# Supplies.net
KiCad netlist of a schematic drawn in Altium Designer
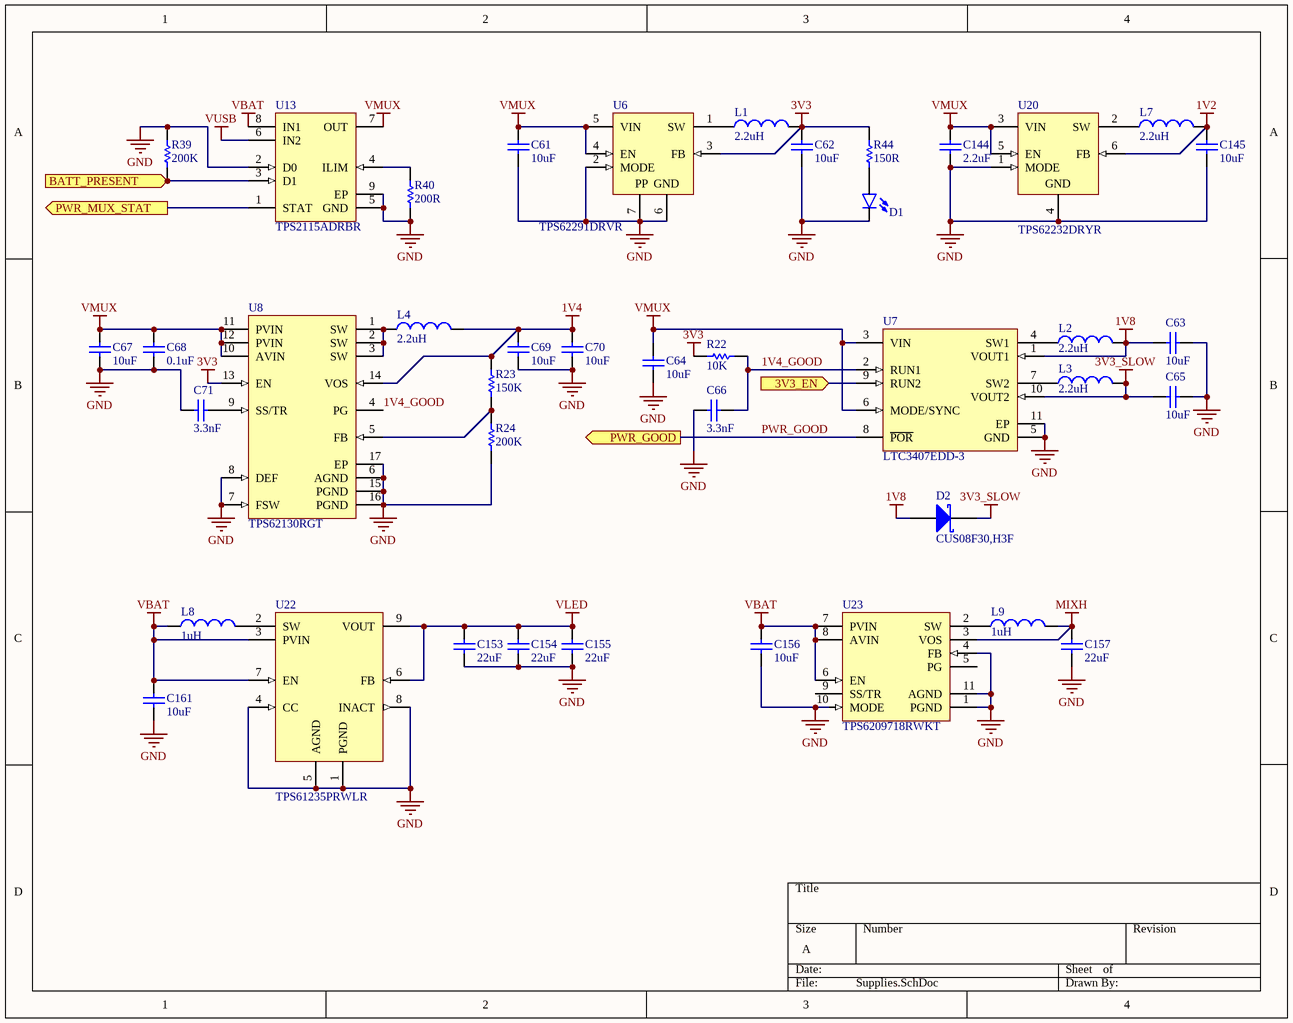
[diagram p0: Supplies.SchDoc]

(export (version "E")
  (design (tool "Eeschema 10.0.6"))
  (components
    (comp (ref "C61")
      (value "10uF")
      (footprint "C0402[1005X55]")
      (description "10uF 6.3V 20% 0402 (1005 Metric)")
      (fields (field (name "TOLERANCE") "20%") (field (name "PARTNUMBER") "GRM155R60J106ME44D"))
      (libsource (lib "Capacitors") (part "CAP_10uF_6.3V_0402_20%"))
    )
    (comp (ref "C62")
      (value "10uF")
      (footprint "C0402[1005X55]")
      (description "10uF 6.3V 20% 0402 (1005 Metric)")
      (fields (field (name "TOLERANCE") "20%") (field (name "PARTNUMBER") "GRM155R60J106ME44D"))
      (libsource (lib "Capacitors") (part "CAP_10uF_6.3V_0402_20%"))
    )
    (comp (ref "C63")
      (value "10uF")
      (footprint "C0402[1005X55]")
      (description "10uF 6.3V 20% 0402 (1005 Metric)")
      (fields (field (name "PARTNUMBER") "GRM155R60J106ME44D") (field (name "MANUFACTURER") "Murata"))
      (libsource (lib "Capacitors") (part "CAP_10uF_6.3V_0402_20%"))
    )
    (comp (ref "C64")
      (value "10uF")
      (footprint "C0402[1005X55]")
      (description "10uF 6.3V 20% 0402 (1005 Metric)")
      (fields (field (name "PARTNUMBER") "GRM155R60J106ME44D") (field (name "MANUFACTURER") "Murata"))
      (libsource (lib "Capacitors") (part "CAP_10uF_6.3V_0402_20%"))
    )
    (comp (ref "C65")
      (value "10uF")
      (footprint "C0402[1005X55]")
      (description "10uF 6.3V 20% 0402 (1005 Metric)")
      (fields (field (name "PARTNUMBER") "GRM155R60J106ME44D") (field (name "MANUFACTURER") "Murata"))
      (libsource (lib "Capacitors") (part "CAP_10uF_6.3V_0402_20%"))
    )
    (comp (ref "C66")
      (value "3.3nF")
      (footprint "C0402[1005X55]")
      (description "3.3nF 50V 10% 0402 (1005 Metric)")
      (fields (field (name "PARTNUMBER") "GRM155R71H332KA01D") (field (name "MANUFACTURER") "Murata"))
      (libsource (lib "Capacitors") (part "CAP_3.3nF_50V_0402_10%"))
    )
    (comp (ref "C67")
      (value "10uF")
      (footprint "C0402[1005X55]")
      (description "10uF 6.3V 20% 0402 (1005 Metric)")
      (fields (field (name "PARTNUMBER") "GRM155R60J106ME44D") (field (name "MANUFACTURER") "Murata"))
      (libsource (lib "Capacitors") (part "CAP_10uF_6.3V_0402_20%"))
    )
    (comp (ref "C68")
      (value "0.1uF")
      (footprint "C0402[1005X55]")
      (description "0.1uF 6.3V 10% 0402 (1005 Metric)")
      (fields (field (name "PARTNUMBER") "GRM155R70J104KA01D") (field (name "MANUFACTURER") "Murata"))
      (libsource (lib "Capacitors") (part "CAP_0.1uF_6.3V_0402_10%"))
    )
    (comp (ref "C69")
      (value "10uF")
      (footprint "C0402[1005X55]")
      (description "10uF 6.3V 20% 0402 (1005 Metric)")
      (fields (field (name "PARTNUMBER") "GRM155R60J106ME44D") (field (name "MANUFACTURER") "Murata"))
      (libsource (lib "Capacitors") (part "CAP_10uF_6.3V_0402_20%"))
    )
    (comp (ref "C70")
      (value "10uF")
      (footprint "C0402[1005X55]")
      (description "10uF 6.3V 20% 0402 (1005 Metric)")
      (fields (field (name "PARTNUMBER") "GRM155R60J106ME44D") (field (name "MANUFACTURER") "Murata"))
      (libsource (lib "Capacitors") (part "CAP_10uF_6.3V_0402_20%"))
    )
    (comp (ref "C71")
      (value "3.3nF")
      (footprint "C0402[1005X55]")
      (description "3.3nF 50V 10% 0402 (1005 Metric)")
      (fields (field (name "PARTNUMBER") "GRM155R71H332KA01D") (field (name "MANUFACTURER") "Murata"))
      (libsource (lib "Capacitors") (part "CAP_3.3nF_50V_0402_10%"))
    )
    (comp (ref "C144")
      (value "2.2uF")
      (footprint "C0402[1005X55]")
      (description "2.2uF 6.3V 20% 0402 (1005 Metric)")
      (fields (field (name "PARTNUMBER") "GRM155R60J225ME15D") (field (name "MANUFACTURER") "Murata"))
      (libsource (lib "Capacitors") (part "CAP_2.2uF_6.3V_0402_20%"))
    )
    (comp (ref "C145")
      (value "10uF")
      (footprint "C0402[1005X55]")
      (description "10uF 6.3V 20% 0402 (1005 Metric)")
      (fields (field (name "PARTNUMBER") "GRM155R60J106ME44D") (field (name "MANUFACTURER") "Murata"))
      (libsource (lib "Capacitors") (part "CAP_10uF_6.3V_0402_20%"))
    )
    (comp (ref "C153")
      (value "22uF")
      (footprint "C0603[1608X92]")
      (description "22uF 6.3V 10% 0603 (1608 Metric)")
      (fields (field (name "PARTNUMBER") "GRT188R60J226ME13D") (field (name "MANUFACTURER") "Murata"))
      (libsource (lib "Capacitors") (part "CAP_22uF_6.3V_0603_10%"))
    )
    (comp (ref "C154")
      (value "22uF")
      (footprint "C0603[1608X92]")
      (description "22uF 6.3V 10% 0603 (1608 Metric)")
      (fields (field (name "PARTNUMBER") "GRT188R60J226ME13D") (field (name "MANUFACTURER") "Murata"))
      (libsource (lib "Capacitors") (part "CAP_22uF_6.3V_0603_10%"))
    )
    (comp (ref "C155")
      (value "22uF")
      (footprint "C0603[1608X92]")
      (description "22uF 6.3V 10% 0603 (1608 Metric)")
      (fields (field (name "PARTNUMBER") "GRT188R60J226ME13D") (field (name "MANUFACTURER") "Murata"))
      (libsource (lib "Capacitors") (part "CAP_22uF_6.3V_0603_10%"))
    )
    (comp (ref "C156")
      (value "10uF")
      (footprint "C0402[1005X55]")
      (description "10uF 6.3V 20% 0402 (1005 Metric)")
      (fields (field (name "PARTNUMBER") "GRM155R60J106ME44D") (field (name "MANUFACTURER") "Murata"))
      (libsource (lib "Capacitors") (part "CAP_10uF_6.3V_0402_20%"))
    )
    (comp (ref "C157")
      (value "22uF")
      (footprint "C0603[1608X92]")
      (description "22uF 6.3V 10% 0603 (1608 Metric)")
      (fields (field (name "PARTNUMBER") "GRT188R60J226ME13D") (field (name "MANUFACTURER") "Murata"))
      (libsource (lib "Capacitors") (part "CAP_22uF_6.3V_0603_10%"))
    )
    (comp (ref "C161")
      (value "10uF")
      (footprint "C0402[1005X55]")
      (description "10uF 6.3V 20% 0402 (1005 Metric)")
      (fields (field (name "PARTNUMBER") "GRM155R60J106ME44D") (field (name "MANUFACTURER") "Murata"))
      (libsource (lib "Capacitors") (part "CAP_10uF_6.3V_0402_20%"))
    )
    (comp (ref "D1")
      (value "LED_0603_BLUE_5mA")
      (footprint "LED0603")
      (fields (field (name "PARTNUMBER") "LTST-C193TBKT-5A") (field (name "MANUFACTURER") "Lite-On Inc."))
      (libsource (lib "LEDs") (part "LED_0603_BLUE_5mA"))
    )
    (comp (ref "D2")
      (value "CUS08F30,H3F")
      (footprint "SOD-323")
      (fields (field (name "MANUFACTURER") "Toshiba"))
      (libsource (lib "Diodes") (part "CUS08F30,H3F"))
    )
    (comp (ref "L1")
      (value "2.2uH")
      (footprint "IND0805")
      (description "2.2uH 20% 1.7A 0805")
      (fields (field (name "PARTNUMBER") "LQM21PN2R2MGHL") (field (name "MANUFACTURER") "Murata"))
      (libsource (lib "Inductors") (part "IND_2.2uH_1.7A_0805_20%"))
    )
    (comp (ref "L2")
      (value "2.2uH")
      (footprint "IND0603")
      (description "2.2uH 20% 750mA 0603")
      (fields (field (name "PARTNUMBER") "LQM18PZ2R2MCHD") (field (name "MANUFACTURER") "Murata"))
      (libsource (lib "Inductors") (part "IND_2.2uH_750mA_0603_20%"))
    )
    (comp (ref "L3")
      (value "2.2uH")
      (footprint "IND0603")
      (description "2.2uH 20% 750mA 0603")
      (fields (field (name "PARTNUMBER") "LQM18PZ2R2MCHD") (field (name "MANUFACTURER") "Murata"))
      (libsource (lib "Inductors") (part "IND_2.2uH_750mA_0603_20%"))
    )
    (comp (ref "L4")
      (value "2.2uH")
      (footprint "IND1008")
      (description "2.2uH 20% 3.3A 1008")
      (fields (field (name "PARTNUMBER") "DFE252012F-2R2M=P2") (field (name "MANUFACTURER") "Murata"))
      (libsource (lib "Inductors") (part "IND_2.2uH_3.3A_1008_20%"))
    )
    (comp (ref "L7")
      (value "2.2uH")
      (footprint "IND0603")
      (description "2.2uH 20% 750mA 0603")
      (fields (field (name "PARTNUMBER") "LQM18PZ2R2MCHD") (field (name "MANUFACTURER") "Murata"))
      (libsource (lib "Inductors") (part "IND_2.2uH_750mA_0603_20%"))
    )
    (comp (ref "L8")
      (value "1uH")
      (footprint "IND1008")
      (description "1uH 20% 4.7A 1008")
      (fields (field (name "PARTNUMBER") "DFE252012F-2R2M=P2") (field (name "MANUFACTURER") "Murata"))
      (libsource (lib "Inductors") (part "IND_1uH_4.7A_1008_20%"))
    )
    (comp (ref "L9")
      (value "1uH")
      (footprint "IND0805")
      (description "1uH 20% 2.3A 0805")
      (fields (field (name "PARTNUMBER") "DFE201210S-1R0M=P2") (field (name "MANUFACTURER") "Murata"))
      (libsource (lib "Inductors") (part "IND_1uH_2.3A_0805_20%"))
    )
    (comp (ref "R22")
      (value "10K")
      (footprint "R0402[1005]")
      (description "10K 0.063W 1% 0402 (1005 Metric)")
      (fields (field (name "MANUFACTURER") "KOA Speer") (field (name "PARTNUMBER") "RK73H1ETTP1002F"))
      (libsource (lib "Resistors") (part "RES_10K_0402_1%"))
    )
    (comp (ref "R23")
      (value "150K")
      (footprint "R0402[1005]")
      (description "150K 0.063W 1% 0402 (1005 Metric)")
      (fields (field (name "MANUFACTURER") "KOA Speer") (field (name "PARTNUMBER") "RK73H1ETTP1503F"))
      (libsource (lib "Resistors") (part "RES_150K_0402_1%"))
    )
    (comp (ref "R24")
      (value "200K")
      (footprint "R0402[1005]")
      (description "200K 0.063W 1% 0402 (1005 Metric)")
      (fields (field (name "MANUFACTURER") "KOA Speer") (field (name "PARTNUMBER") "RK73H1ETTP2003F"))
      (libsource (lib "Resistors") (part "RES_200K_0402_1%"))
    )
    (comp (ref "R39")
      (value "200K")
      (footprint "R0402[1005]")
      (description "200K 0.063W 1% 0402 (1005 Metric)")
      (fields (field (name "MANUFACTURER") "KOA Speer") (field (name "PARTNUMBER") "RK73H1ETTP2003F"))
      (libsource (lib "Resistors") (part "RES_200K_0402_1%"))
    )
    (comp (ref "R40")
      (value "200R")
      (footprint "R0402[1005]")
      (description "200R 0.063W 1% 0402 (1005 Metric)")
      (fields (field (name "MANUFACTURER") "KOA Speer") (field (name "PARTNUMBER") "RK73H1ETTP2000F"))
      (libsource (lib "Resistors") (part "RES_200R_0402_1%"))
    )
    (comp (ref "R44")
      (value "150R")
      (footprint "R0402[1005]")
      (description "150R 0.063W 1% 0402 (1005 Metric)")
      (fields (field (name "MANUFACTURER") "KOA Speer") (field (name "PARTNUMBER") "RK73H1ETTP1500F"))
      (libsource (lib "Resistors") (part "RES_150R_0402_1%"))
    )
    (comp (ref "U6")
      (value "TPS62291DRVR")
      (footprint "WSON-6")
      (description "Voltage Regulators - Switching Regulators 2.25MHz 1A Step-Down Cnvrtr 3.3V Output")
      (fields (field (name "MANUFACTURER") "Texas Instruments"))
      (libsource (lib "ICs") (part "TPS62291DRVR"))
    )
    (comp (ref "U7")
      (value "LTC3407EDD-3")
      (footprint "VSON-10 (3mmx3mm)")
      (fields (field (name "MANUFACTURER") "Linear Technology"))
      (libsource (lib "ICs") (part "LTC3407EDD-3"))
    )
    (comp (ref "U8")
      (value "TPS62130RGT")
      (footprint "QFN-16")
      (fields (field (name "MANUFACTURER") "Texas Instruments"))
      (libsource (lib "ICs") (part "TPS62130RGT"))
    )
    (comp (ref "U13")
      (value "TPS2115ADRBR")
      (footprint "VSON-8 (3x3MM)")
      (description "Power Switch ICs - Power Distribution Autoswitching Pwr Mux")
      (fields (field (name "MANUFACTURER") "Texas Instruments"))
      (libsource (lib "ICs") (part "TPS2115ADRBR"))
    )
    (comp (ref "U20")
      (value "TPS62232DRYR")
      (footprint "USON-6")
      (description "Switching Voltage Regulators 3 MHz Ultra Small Step Down Converter")
      (fields (field (name "MANUFACTURER") "Texas Instruments"))
      (libsource (lib "ICs") (part "TPS62232DRYR"))
    )
    (comp (ref "U22")
      (value "TPS61235PRWLR")
      (footprint "VQFN-9")
      (fields (field (name "MANUFACTURER") "Texas Instruments"))
      (libsource (lib "ICs") (part "TPS61235PRWLR"))
    )
    (comp (ref "U23")
      (value "TPS6209718RWKT")
      (footprint "VQFN-11")
      (fields (field (name "MANUFACTURER") "Texas Instruments"))
      (libsource (lib "ICs") (part "TPS6209718RWKT"))
    )
  )
  (nets
    (net (code "1") (name "/1V4_GOOD") (class "Default")
      (node (ref "C66") (pin "2") (pinfunction "2_2") (pintype "passive"))
      (node (ref "R22") (pin "2") (pinfunction "2_2") (pintype "passive"))
      (node (ref "U7") (pin "2") (pinfunction "RUN1_2") (pintype "input"))
      (node (ref "U8") (pin "4") (pinfunction "PG_4") (pintype "tri_state"))
    )
    (net (code "2") (name "/3V3_EN") (class "Default")
      (node (ref "U7") (pin "9") (pinfunction "RUN2_9") (pintype "input"))
    )
    (net (code "3") (name "/BATT_PRESENT") (class "Default")
      (node (ref "R39") (pin "1") (pinfunction "1_1") (pintype "passive"))
      (node (ref "U13") (pin "3") (pinfunction "D1_3") (pintype "input"))
    )
    (net (code "4") (name "/PWR_GOOD") (class "Default")
      (node (ref "U7") (pin "8") (pinfunction "~{POR}_8") (pintype "open_collector"))
    )
    (net (code "5") (name "/PWR_MUX_STAT") (class "Default")
      (node (ref "U13") (pin "1") (pinfunction "STAT_1") (pintype "tri_state"))
    )
    (net (code "6") (name "1V2") (class "Default")
      (node (ref "C145") (pin "2") (pinfunction "2_2") (pintype "passive"))
      (node (ref "L7") (pin "2") (pinfunction "2_2") (pintype "passive"))
      (node (ref "U20") (pin "6") (pinfunction "FB_6") (pintype "input"))
    )
    (net (code "7") (name "1V4") (class "Default")
      (node (ref "C69") (pin "2") (pinfunction "2_2") (pintype "passive"))
      (node (ref "C70") (pin "2") (pinfunction "2_2") (pintype "passive"))
      (node (ref "L4") (pin "2") (pinfunction "2_2") (pintype "passive"))
      (node (ref "R23") (pin "2") (pinfunction "2_2") (pintype "passive"))
      (node (ref "U8") (pin "14") (pinfunction "VOS_14") (pintype "input"))
    )
    (net (code "8") (name "1V8") (class "Default")
      (node (ref "C63") (pin "2") (pinfunction "2_2") (pintype "passive"))
      (node (ref "D2") (pin "2") (pinfunction "A_2") (pintype "passive"))
      (node (ref "L2") (pin "2") (pinfunction "2_2") (pintype "passive"))
      (node (ref "U7") (pin "1") (pinfunction "VOUT1_1") (pintype "input"))
    )
    (net (code "9") (name "3V3") (class "Default")
      (node (ref "C62") (pin "2") (pinfunction "2_2") (pintype "passive"))
      (node (ref "L1") (pin "2") (pinfunction "2_2") (pintype "passive"))
      (node (ref "R22") (pin "1") (pinfunction "1_1") (pintype "passive"))
      (node (ref "R44") (pin "2") (pinfunction "2_2") (pintype "passive"))
      (node (ref "U6") (pin "3") (pinfunction "FB_3") (pintype "input"))
      (node (ref "U8") (pin "13") (pinfunction "EN_13") (pintype "input"))
    )
    (net (code "10") (name "3V3_SLOW") (class "Default")
      (node (ref "C65") (pin "1") (pinfunction "1_1") (pintype "passive"))
      (node (ref "D2") (pin "1") (pinfunction "K_1") (pintype "passive"))
      (node (ref "L3") (pin "2") (pinfunction "2_2") (pintype "passive"))
      (node (ref "U7") (pin "10") (pinfunction "VOUT2_10") (pintype "input"))
    )
    (net (code "11") (name "GND") (class "Default")
      (node (ref "C144") (pin "1") (pinfunction "1_1") (pintype "passive"))
      (node (ref "C145") (pin "1") (pinfunction "1_1") (pintype "passive"))
      (node (ref "C153") (pin "1") (pinfunction "1_1") (pintype "passive"))
      (node (ref "C154") (pin "1") (pinfunction "1_1") (pintype "passive"))
      (node (ref "C155") (pin "1") (pinfunction "1_1") (pintype "passive"))
      (node (ref "C156") (pin "1") (pinfunction "1_1") (pintype "passive"))
      (node (ref "C157") (pin "1") (pinfunction "1_1") (pintype "passive"))
      (node (ref "C161") (pin "1") (pinfunction "1_1") (pintype "passive"))
      (node (ref "C61") (pin "1") (pinfunction "1_1") (pintype "passive"))
      (node (ref "C62") (pin "1") (pinfunction "1_1") (pintype "passive"))
      (node (ref "C63") (pin "1") (pinfunction "1_1") (pintype "passive"))
      (node (ref "C64") (pin "1") (pinfunction "1_1") (pintype "passive"))
      (node (ref "C65") (pin "2") (pinfunction "2_2") (pintype "passive"))
      (node (ref "C66") (pin "1") (pinfunction "1_1") (pintype "passive"))
      (node (ref "C67") (pin "1") (pinfunction "1_1") (pintype "passive"))
      (node (ref "C68") (pin "1") (pinfunction "1_1") (pintype "passive"))
      (node (ref "C69") (pin "1") (pinfunction "1_1") (pintype "passive"))
      (node (ref "C70") (pin "1") (pinfunction "1_1") (pintype "passive"))
      (node (ref "C71") (pin "1") (pinfunction "1_1") (pintype "passive"))
      (node (ref "D1") (pin "C") (pinfunction "C_C") (pintype "passive"))
      (node (ref "R24") (pin "1") (pinfunction "1_1") (pintype "passive"))
      (node (ref "R39") (pin "2") (pinfunction "2_2") (pintype "passive"))
      (node (ref "R40") (pin "1") (pinfunction "1_1") (pintype "passive"))
      (node (ref "U13") (pin "2") (pinfunction "D0_2") (pintype "input"))
      (node (ref "U13") (pin "5") (pinfunction "GND_5") (pintype "power_in"))
      (node (ref "U13") (pin "9") (pinfunction "EP_9") (pintype "power_in"))
      (node (ref "U20") (pin "1") (pinfunction "MODE_1") (pintype "input"))
      (node (ref "U20") (pin "4") (pinfunction "GND_4") (pintype "power_in"))
      (node (ref "U22") (pin "1") (pinfunction "PGND_1") (pintype "power_in"))
      (node (ref "U22") (pin "4") (pinfunction "CC_4") (pintype "input"))
      (node (ref "U22") (pin "5") (pinfunction "AGND_5") (pintype "power_in"))
      (node (ref "U22") (pin "8") (pinfunction "INACT_8") (pintype "output"))
      (node (ref "U23") (pin "1") (pinfunction "PGND_1") (pintype "power_in"))
      (node (ref "U23") (pin "10") (pinfunction "MODE_10") (pintype "input"))
      (node (ref "U23") (pin "11") (pinfunction "AGND_11") (pintype "power_in"))
      (node (ref "U23") (pin "4") (pinfunction "FB_4") (pintype "input"))
      (node (ref "U6") (pin "2") (pinfunction "MODE_2") (pintype "input"))
      (node (ref "U6") (pin "6") (pinfunction "GND_6") (pintype "power_in"))
      (node (ref "U6") (pin "7") (pinfunction "EP_7") (pintype "passive"))
      (node (ref "U7") (pin "11") (pinfunction "EP_11") (pintype "power_in"))
      (node (ref "U7") (pin "5") (pinfunction "GND_5") (pintype "power_in"))
      (node (ref "U8") (pin "15") (pinfunction "PGND_15") (pintype "power_in"))
      (node (ref "U8") (pin "16") (pinfunction "PGND_16") (pintype "power_in"))
      (node (ref "U8") (pin "17") (pinfunction "EP_17") (pintype "power_in"))
      (node (ref "U8") (pin "6") (pinfunction "AGND_6") (pintype "power_in"))
      (node (ref "U8") (pin "7") (pinfunction "FSW_7") (pintype "input"))
      (node (ref "U8") (pin "8") (pinfunction "DEF_8") (pintype "input"))
    )
    (net (code "12") (name "MIXH") (class "Default")
      (node (ref "C157") (pin "2") (pinfunction "2_2") (pintype "passive"))
      (node (ref "L9") (pin "2") (pinfunction "2_2") (pintype "passive"))
      (node (ref "U23") (pin "3") (pinfunction "VOS_3") (pintype "passive"))
    )
    (net (code "13") (name "Net-(D1-PadA)") (class "Default")
      (node (ref "D1") (pin "A") (pinfunction "A_A") (pintype "passive"))
      (node (ref "R44") (pin "1") (pinfunction "1_1") (pintype "passive"))
    )
    (net (code "14") (name "Net-(L4-Pad1)") (class "Default")
      (node (ref "L4") (pin "1") (pinfunction "1_1") (pintype "passive"))
      (node (ref "U8") (pin "1") (pinfunction "SW_1") (pintype "power_in"))
      (node (ref "U8") (pin "2") (pinfunction "SW_2") (pintype "power_in"))
      (node (ref "U8") (pin "3") (pinfunction "SW_3") (pintype "power_in"))
    )
    (net (code "15") (name "Net-(U6-SW)") (class "Default")
      (node (ref "L1") (pin "1") (pinfunction "1_1") (pintype "passive"))
      (node (ref "U6") (pin "1") (pinfunction "SW_1") (pintype "power_in"))
    )
    (net (code "16") (name "Net-(U7-SW1)") (class "Default")
      (node (ref "L2") (pin "1") (pinfunction "1_1") (pintype "passive"))
      (node (ref "U7") (pin "4") (pinfunction "SW1_4") (pintype "power_in"))
    )
    (net (code "17") (name "Net-(U7-SW2)") (class "Default")
      (node (ref "L3") (pin "1") (pinfunction "1_1") (pintype "passive"))
      (node (ref "U7") (pin "7") (pinfunction "SW2_7") (pintype "power_in"))
    )
    (net (code "18") (name "Net-(U8-FB)") (class "Default")
      (node (ref "R23") (pin "1") (pinfunction "1_1") (pintype "passive"))
      (node (ref "R24") (pin "2") (pinfunction "2_2") (pintype "passive"))
      (node (ref "U8") (pin "5") (pinfunction "FB_5") (pintype "input"))
    )
    (net (code "19") (name "Net-(U8-SS{slash}TR)") (class "Default")
      (node (ref "C71") (pin "2") (pinfunction "2_2") (pintype "passive"))
      (node (ref "U8") (pin "9") (pinfunction "SS/TR_9") (pintype "input"))
    )
    (net (code "20") (name "Net-(U13-ILIM)") (class "Default")
      (node (ref "R40") (pin "2") (pinfunction "2_2") (pintype "passive"))
      (node (ref "U13") (pin "4") (pinfunction "ILIM_4") (pintype "input"))
    )
    (net (code "21") (name "Net-(U20-SW)") (class "Default")
      (node (ref "L7") (pin "1") (pinfunction "1_1") (pintype "passive"))
      (node (ref "U20") (pin "2") (pinfunction "SW_2") (pintype "power_in"))
    )
    (net (code "22") (name "Net-(U22-SW)") (class "Default")
      (node (ref "L8") (pin "2") (pinfunction "2_2") (pintype "passive"))
      (node (ref "U22") (pin "2") (pinfunction "SW_2") (pintype "power_in"))
    )
    (net (code "23") (name "Net-(U23-SW)") (class "Default")
      (node (ref "L9") (pin "1") (pinfunction "1_1") (pintype "passive"))
      (node (ref "U23") (pin "2") (pinfunction "SW_2") (pintype "power_in"))
    )
    (net (code "24") (name "VBAT") (class "Default")
      (node (ref "C156") (pin "2") (pinfunction "2_2") (pintype "passive"))
      (node (ref "C161") (pin "2") (pinfunction "2_2") (pintype "passive"))
      (node (ref "L8") (pin "1") (pinfunction "1_1") (pintype "passive"))
      (node (ref "U13") (pin "8") (pinfunction "IN1_8") (pintype "power_in"))
      (node (ref "U22") (pin "3") (pinfunction "PVIN_3") (pintype "power_in"))
      (node (ref "U22") (pin "7") (pinfunction "EN_7") (pintype "input"))
      (node (ref "U23") (pin "6") (pinfunction "EN_6") (pintype "input"))
      (node (ref "U23") (pin "7") (pinfunction "PVIN_7") (pintype "power_in"))
      (node (ref "U23") (pin "8") (pinfunction "AVIN_8") (pintype "power_in"))
    )
    (net (code "25") (name "VLED") (class "Default")
      (node (ref "C153") (pin "2") (pinfunction "2_2") (pintype "passive"))
      (node (ref "C154") (pin "2") (pinfunction "2_2") (pintype "passive"))
      (node (ref "C155") (pin "2") (pinfunction "2_2") (pintype "passive"))
      (node (ref "U22") (pin "6") (pinfunction "FB_6") (pintype "input"))
      (node (ref "U22") (pin "9") (pinfunction "VOUT_9") (pintype "power_in"))
    )
    (net (code "26") (name "VMUX") (class "Default")
      (node (ref "C144") (pin "2") (pinfunction "2_2") (pintype "passive"))
      (node (ref "C61") (pin "2") (pinfunction "2_2") (pintype "passive"))
      (node (ref "C64") (pin "2") (pinfunction "2_2") (pintype "passive"))
      (node (ref "C67") (pin "2") (pinfunction "2_2") (pintype "passive"))
      (node (ref "C68") (pin "2") (pinfunction "2_2") (pintype "passive"))
      (node (ref "U13") (pin "7") (pinfunction "OUT_7") (pintype "power_in"))
      (node (ref "U20") (pin "3") (pinfunction "VIN_3") (pintype "power_in"))
      (node (ref "U20") (pin "5") (pinfunction "EN_5") (pintype "input"))
      (node (ref "U6") (pin "4") (pinfunction "EN_4") (pintype "input"))
      (node (ref "U6") (pin "5") (pinfunction "VIN_5") (pintype "power_in"))
      (node (ref "U7") (pin "3") (pinfunction "VIN_3") (pintype "power_in"))
      (node (ref "U7") (pin "6") (pinfunction "MODE/SYNC_6") (pintype "input"))
      (node (ref "U8") (pin "10") (pinfunction "AVIN_10") (pintype "power_in"))
      (node (ref "U8") (pin "11") (pinfunction "PVIN_11") (pintype "power_in"))
      (node (ref "U8") (pin "12") (pinfunction "PVIN_12") (pintype "power_in"))
    )
    (net (code "27") (name "VUSB") (class "Default")
      (node (ref "U13") (pin "6") (pinfunction "IN2_6") (pintype "power_in"))
    )
    (net (code "28") (name "unconnected-(U23-PG-Pad5)") (class "Default")
      (node (ref "U23") (pin "5") (pinfunction "PG_5") (pintype "passive"))
    )
    (net (code "29") (name "unconnected-(U23-SS{slash}TR-Pad9)") (class "Default")
      (node (ref "U23") (pin "9") (pinfunction "SS/TR_9") (pintype "passive"))
    )
  )
)
